# OpAmp-Inverting-3Transistor.net
KiCad netlist of a schematic drawn in EAGLE
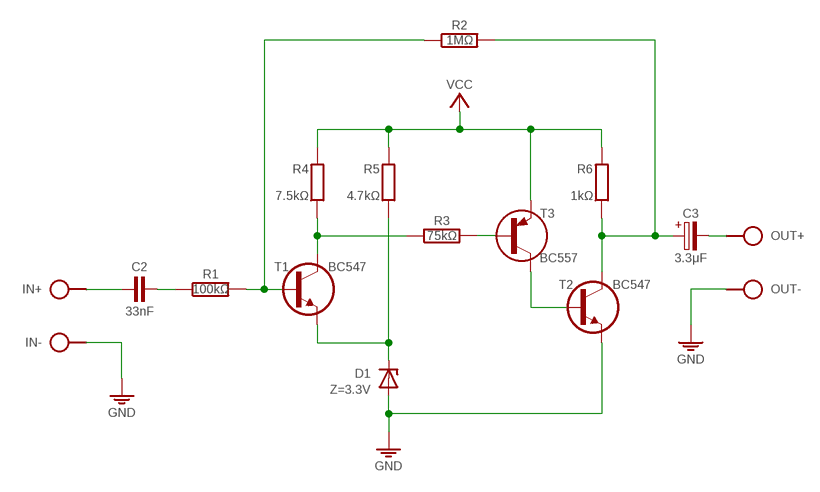
[diagram p0: schematic, sheet 1]

(export (version "E")
  (design (tool "Eeschema 10.0.6"))
  (components
    (comp (ref "C2")
      (value "33nF")
      (footprint "eagle-import:C050-020X044")
      (libsource (lib "eagle-import") (part "C050-020X044"))
    )
    (comp (ref "C3")
      (value "3.3μF")
      (footprint "eagle-import:E2.5-4_V")
      (libsource (lib "eagle-import") (part "CPOLE2,5-4/V"))
    )
    (comp (ref "D1")
      (value "Z=3.3V")
      (footprint "eagle-import:DO34Z2,5")
      (libsource (lib "eagle-import") (part "Z-DIODE34Z2,5"))
    )
    (comp (ref "IN")
      (value "SPAD+--+")
      (footprint "eagle-import:SPAD-+")
      (libsource (lib "eagle-import") (part "SPAD+--+"))
    )
    (comp (ref "J1")
      (value "VCC_GNDPWR-R")
      (footprint "eagle-import:PWR-R")
      (libsource (lib "eagle-import") (part "VCC_GNDPWR-R"))
    )
    (comp (ref "OUT")
      (value "SPAD+-+-")
      (footprint "eagle-import:SPAD+-")
      (libsource (lib "eagle-import") (part "SPAD+-+-"))
    )
    (comp (ref "R1")
      (value "100kΩ")
      (footprint "eagle-import:0204_10")
      (libsource (lib "eagle-import") (part "R-H0204/10"))
    )
    (comp (ref "R2")
      (value "1MΩ")
      (footprint "eagle-import:0204_10")
      (libsource (lib "eagle-import") (part "R-H0204/10"))
    )
    (comp (ref "R3")
      (value "75kΩ")
      (footprint "eagle-import:0204_10")
      (libsource (lib "eagle-import") (part "R-H0204/10"))
    )
    (comp (ref "R4")
      (value "7.5kΩ")
      (footprint "eagle-import:0204_10")
      (libsource (lib "eagle-import") (part "R0204/10"))
    )
    (comp (ref "R5")
      (value "4.7kΩ")
      (footprint "eagle-import:0204_10")
      (libsource (lib "eagle-import") (part "R0204/10"))
    )
    (comp (ref "R6")
      (value "1kΩ")
      (footprint "eagle-import:0204_10-V")
      (libsource (lib "eagle-import") (part "R0204/10-V"))
    )
    (comp (ref "T1")
      (value "BC547")
      (footprint "eagle-import:TO92-CBE")
      (libsource (lib "eagle-import") (part "BC547CBE"))
    )
    (comp (ref "T2")
      (value "BC547")
      (footprint "eagle-import:TO92-CBE")
      (libsource (lib "eagle-import") (part "BC547CBE"))
    )
    (comp (ref "T3")
      (value "BC557")
      (footprint "eagle-import:TO92-CBE")
      (libsource (lib "eagle-import") (part "BC557CBE"))
    )
  )
  (nets
    (net (code "1") (name "GND") (class "Default")
      (node (ref "D1") (pin "A") (pinfunction "A_A") (pintype "passive"))
      (node (ref "IN") (pin "1") (pinfunction "P$1_1") (pintype "passive"))
      (node (ref "J1") (pin "1") (pinfunction "GND_1") (pintype "power_in"))
      (node (ref "OUT") (pin "1") (pinfunction "P$1_1") (pintype "passive"))
      (node (ref "T2") (pin "E") (pinfunction "E_E") (pintype "passive"))
    )
    (net (code "2") (name "Net-(C2-Pad1)") (class "Default")
      (node (ref "C2") (pin "1") (pinfunction "1_1") (pintype "passive"))
      (node (ref "R1") (pin "1") (pinfunction "1_1") (pintype "passive"))
    )
    (net (code "3") (name "Net-(C3-Pad+)") (class "Default")
      (node (ref "C3") (pin "+") (pinfunction "+_+") (pintype "passive"))
      (node (ref "R2") (pin "2") (pinfunction "2_2") (pintype "passive"))
      (node (ref "R6") (pin "2") (pinfunction "2_2") (pintype "passive"))
      (node (ref "T2") (pin "C") (pinfunction "C_C") (pintype "passive"))
    )
    (net (code "4") (name "Net-(D1-PadC)") (class "Default")
      (node (ref "D1") (pin "C") (pinfunction "C_C") (pintype "passive"))
      (node (ref "R5") (pin "2") (pinfunction "2_2") (pintype "passive"))
      (node (ref "T1") (pin "E") (pinfunction "E_E") (pintype "passive"))
    )
    (net (code "5") (name "Net-(INA-P$1)") (class "Default")
      (node (ref "C2") (pin "2") (pinfunction "2_2") (pintype "passive"))
      (node (ref "IN") (pin "2") (pinfunction "P$1_2") (pintype "passive"))
    )
    (net (code "6") (name "Net-(J1A-VCC)") (class "Default")
      (node (ref "J1") (pin "2") (pinfunction "VCC_2") (pintype "power_in"))
      (node (ref "R4") (pin "1") (pinfunction "1_1") (pintype "passive"))
      (node (ref "R5") (pin "1") (pinfunction "1_1") (pintype "passive"))
      (node (ref "R6") (pin "1") (pinfunction "1_1") (pintype "passive"))
      (node (ref "T3") (pin "E") (pinfunction "E_E") (pintype "passive"))
    )
    (net (code "7") (name "Net-(OUTA-P$1)") (class "Default")
      (node (ref "C3") (pin "-") (pinfunction "-_-") (pintype "passive"))
      (node (ref "OUT") (pin "2") (pinfunction "P$1_2") (pintype "passive"))
    )
    (net (code "8") (name "Net-(R1-Pad2)") (class "Default")
      (node (ref "R1") (pin "2") (pinfunction "2_2") (pintype "passive"))
      (node (ref "R2") (pin "1") (pinfunction "1_1") (pintype "passive"))
      (node (ref "T1") (pin "B") (pinfunction "B_B") (pintype "passive"))
    )
    (net (code "9") (name "Net-(R3-Pad1)") (class "Default")
      (node (ref "R3") (pin "1") (pinfunction "1_1") (pintype "passive"))
      (node (ref "R4") (pin "2") (pinfunction "2_2") (pintype "passive"))
      (node (ref "T1") (pin "C") (pinfunction "C_C") (pintype "passive"))
    )
    (net (code "10") (name "Net-(R3-Pad2)") (class "Default")
      (node (ref "R3") (pin "2") (pinfunction "2_2") (pintype "passive"))
      (node (ref "T3") (pin "B") (pinfunction "B_B") (pintype "passive"))
    )
    (net (code "11") (name "Net-(T2-PadB)") (class "Default")
      (node (ref "T2") (pin "B") (pinfunction "B_B") (pintype "passive"))
      (node (ref "T3") (pin "C") (pinfunction "C_C") (pintype "passive"))
    )
  )
)
